# power-manager.net
KiCad netlist of a schematic drawn in EAGLE
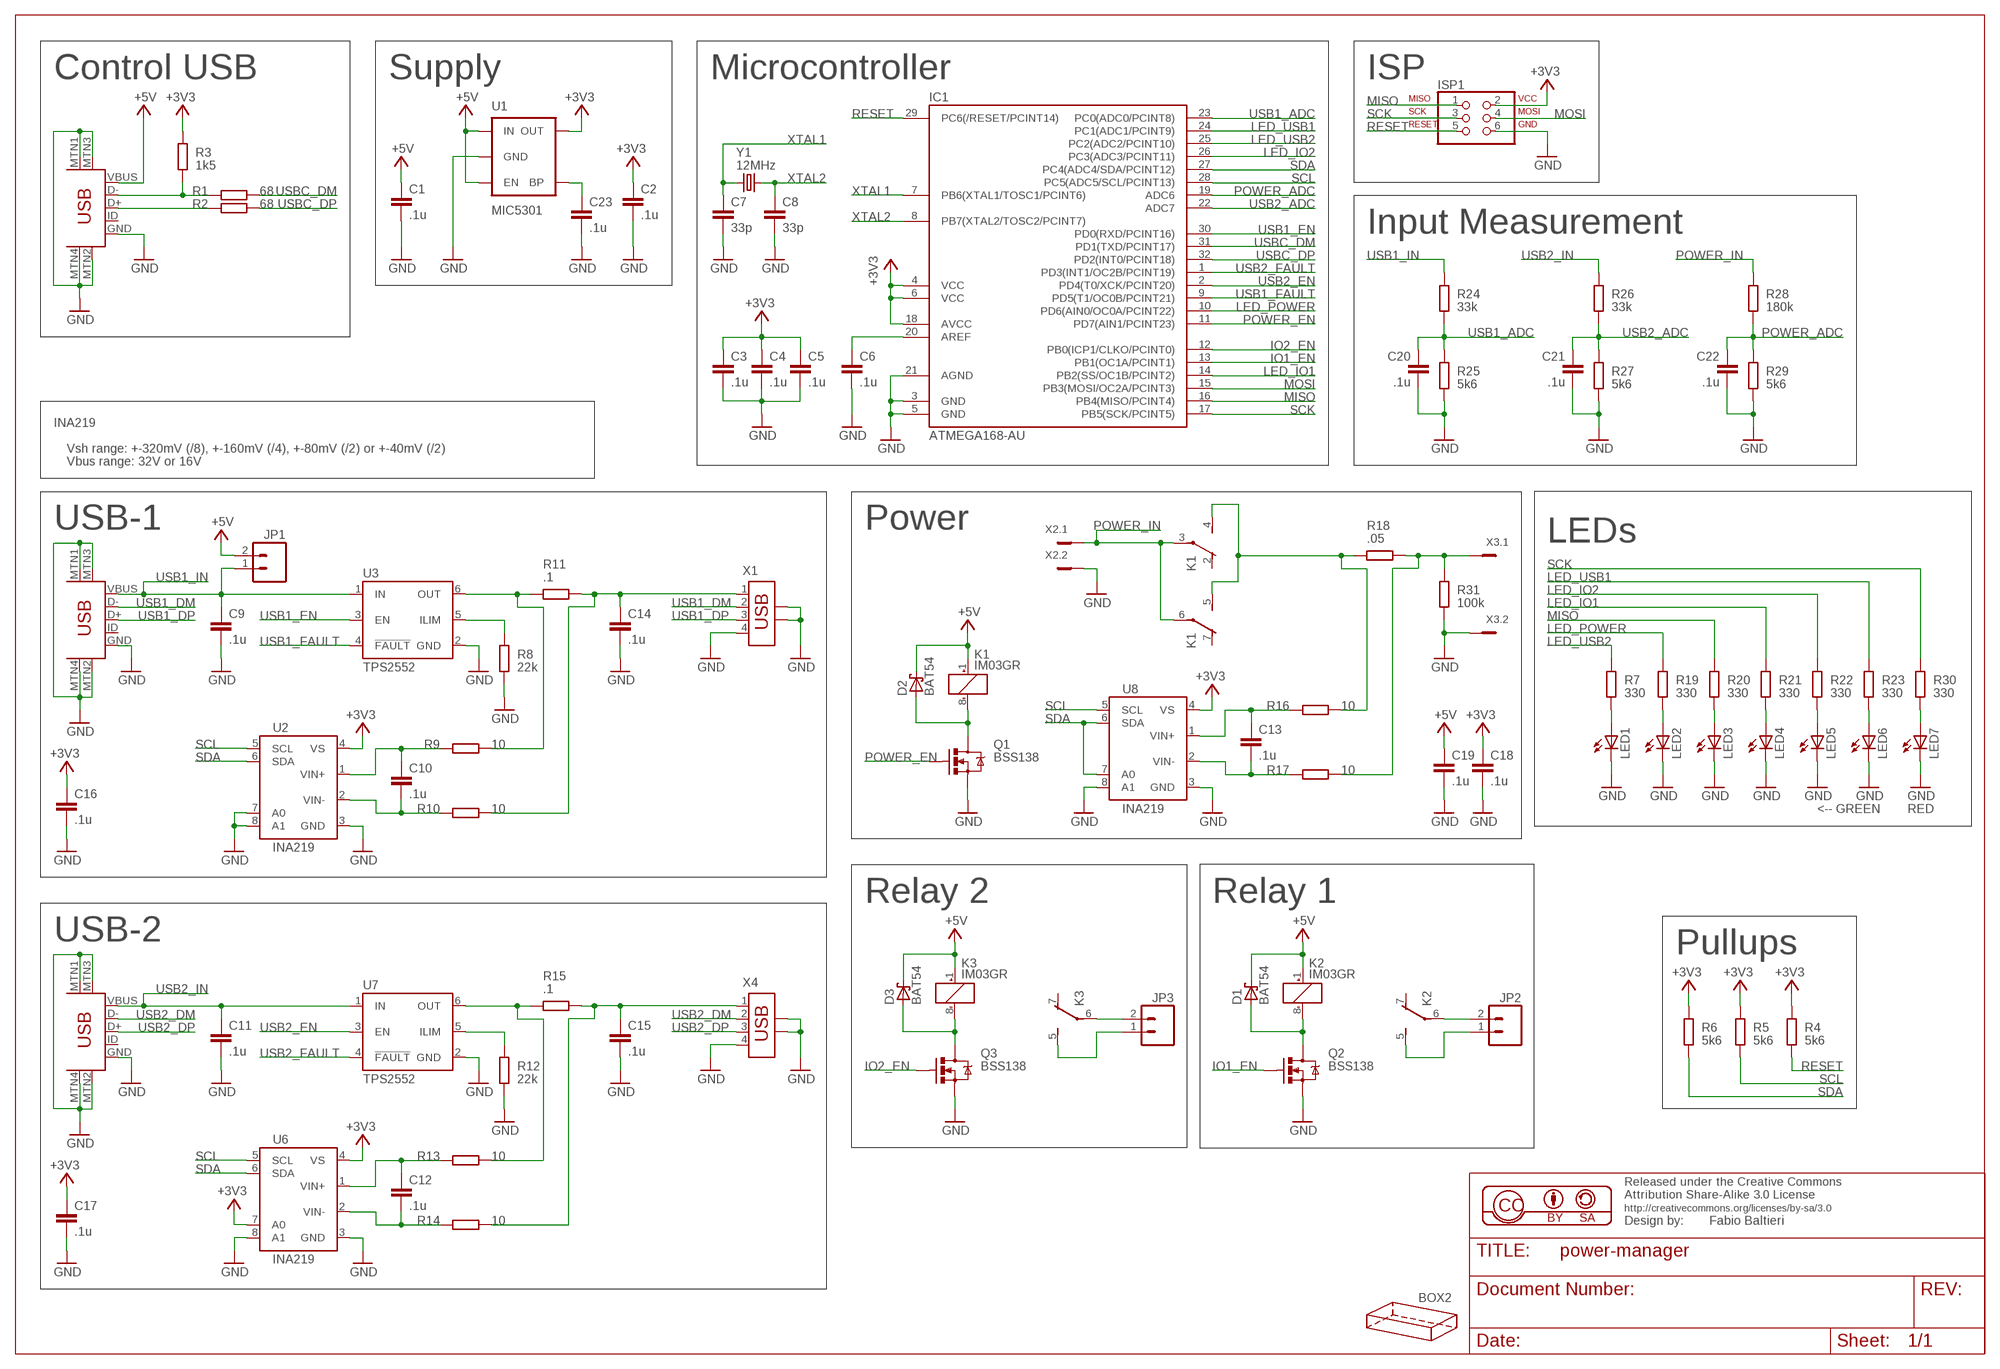
[diagram p0: schematic, sheet 1]

(export (version "E")
  (design (tool "Eeschema 10.0.6"))
  (components
    (comp (ref "BOX2")
      (value "HAMMOND-BOX-K")
      (footprint "eagle-import:1551K")
      (libsource (lib "eagle-import") (part "HAMMOND-BOX-K"))
    )
    (comp (ref "C1")
      (value ".1u")
      (footprint "eagle-import:C0805")
      (libsource (lib "eagle-import") (part "C-EUC0805"))
    )
    (comp (ref "C2")
      (value ".1u")
      (footprint "eagle-import:C0805")
      (libsource (lib "eagle-import") (part "C-EUC0805"))
    )
    (comp (ref "C3")
      (value ".1u")
      (footprint "eagle-import:C0805")
      (libsource (lib "eagle-import") (part "C-EUC0805"))
    )
    (comp (ref "C4")
      (value ".1u")
      (footprint "eagle-import:C0805")
      (libsource (lib "eagle-import") (part "C-EUC0805"))
    )
    (comp (ref "C5")
      (value ".1u")
      (footprint "eagle-import:C0805")
      (libsource (lib "eagle-import") (part "C-EUC0805"))
    )
    (comp (ref "C6")
      (value ".1u")
      (footprint "eagle-import:C0805")
      (libsource (lib "eagle-import") (part "C-EUC0805"))
    )
    (comp (ref "C7")
      (value "33p")
      (footprint "eagle-import:C0805")
      (libsource (lib "eagle-import") (part "C-EUC0805"))
    )
    (comp (ref "C8")
      (value "33p")
      (footprint "eagle-import:C0805")
      (libsource (lib "eagle-import") (part "C-EUC0805"))
    )
    (comp (ref "C9")
      (value ".1u")
      (footprint "eagle-import:C0805")
      (libsource (lib "eagle-import") (part "C-EUC0805"))
    )
    (comp (ref "C10")
      (value ".1u")
      (footprint "eagle-import:C0805")
      (libsource (lib "eagle-import") (part "C-EUC0805"))
    )
    (comp (ref "C11")
      (value ".1u")
      (footprint "eagle-import:C0805")
      (libsource (lib "eagle-import") (part "C-EUC0805"))
    )
    (comp (ref "C12")
      (value ".1u")
      (footprint "eagle-import:C0805")
      (libsource (lib "eagle-import") (part "C-EUC0805"))
    )
    (comp (ref "C13")
      (value ".1u")
      (footprint "eagle-import:C0805")
      (libsource (lib "eagle-import") (part "C-EUC0805"))
    )
    (comp (ref "C14")
      (value ".1u")
      (footprint "eagle-import:C0805")
      (libsource (lib "eagle-import") (part "C-EUC0805"))
    )
    (comp (ref "C15")
      (value ".1u")
      (footprint "eagle-import:C0805")
      (libsource (lib "eagle-import") (part "C-EUC0805"))
    )
    (comp (ref "C16")
      (value ".1u")
      (footprint "eagle-import:C0805")
      (libsource (lib "eagle-import") (part "C-EUC0805"))
    )
    (comp (ref "C17")
      (value ".1u")
      (footprint "eagle-import:C0805")
      (libsource (lib "eagle-import") (part "C-EUC0805"))
    )
    (comp (ref "C18")
      (value ".1u")
      (footprint "eagle-import:C0805")
      (libsource (lib "eagle-import") (part "C-EUC0805"))
    )
    (comp (ref "C19")
      (value ".1u")
      (footprint "eagle-import:C0805")
      (libsource (lib "eagle-import") (part "C-EUC0805"))
    )
    (comp (ref "C20")
      (value ".1u")
      (footprint "eagle-import:C0805")
      (libsource (lib "eagle-import") (part "C-EUC0805"))
    )
    (comp (ref "C21")
      (value ".1u")
      (footprint "eagle-import:C0805")
      (libsource (lib "eagle-import") (part "C-EUC0805"))
    )
    (comp (ref "C22")
      (value ".1u")
      (footprint "eagle-import:C0805")
      (libsource (lib "eagle-import") (part "C-EUC0805"))
    )
    (comp (ref "C23")
      (value ".1u")
      (footprint "eagle-import:C0805")
      (libsource (lib "eagle-import") (part "C-EUC0805"))
    )
    (comp (ref "D1")
      (value "BAT54")
      (footprint "eagle-import:SOT23")
      (libsource (lib "eagle-import") (part "BAT54"))
    )
    (comp (ref "D2")
      (value "BAT54")
      (footprint "eagle-import:SOT23")
      (libsource (lib "eagle-import") (part "BAT54"))
    )
    (comp (ref "D3")
      (value "BAT54")
      (footprint "eagle-import:SOT23")
      (libsource (lib "eagle-import") (part "BAT54"))
    )
    (comp (ref "IC1")
      (value "ATMEGA168-AU")
      (footprint "eagle-import:TQFP32-08")
      (libsource (lib "eagle-import") (part "ATMEGA168-AU"))
    )
    (comp (ref "ISP1")
      (value "ISP-AVR910PTH")
      (footprint "eagle-import:2X03")
      (libsource (lib "eagle-import") (part "ISP-AVR910PTH"))
    )
    (comp (ref "JP1")
      (value "M02PTH")
      (footprint "eagle-import:1X02")
      (libsource (lib "eagle-import") (part "M02PTH"))
    )
    (comp (ref "JP2")
      (value "M02PTH")
      (footprint "eagle-import:1X02")
      (libsource (lib "eagle-import") (part "M02PTH"))
    )
    (comp (ref "JP3")
      (value "M02PTH")
      (footprint "eagle-import:1X02")
      (libsource (lib "eagle-import") (part "M02PTH"))
    )
    (comp (ref "K1")
      (value "IM03GR")
      (footprint "eagle-import:G6J-2FL-Y")
      (fields (field (name "MPN") "G6J-2FL-Y-TR DC4.5"))
      (libsource (lib "eagle-import") (part "G6J-2?-YFL"))
    )
    (comp (ref "K2")
      (value "IM03GR")
      (footprint "eagle-import:G6J-2FL-Y")
      (fields (field (name "MPN") "G6J-2FL-Y-TR DC4.5"))
      (libsource (lib "eagle-import") (part "G6J-2?-YFL"))
    )
    (comp (ref "K3")
      (value "IM03GR")
      (footprint "eagle-import:G6J-2FL-Y")
      (fields (field (name "MPN") "G6J-2FL-Y-TR DC4.5"))
      (libsource (lib "eagle-import") (part "G6J-2?-YFL"))
    )
    (comp (ref "LED1")
      (value "LEDSML0805")
      (footprint "eagle-import:SML0805")
      (libsource (lib "eagle-import") (part "LEDSML0805"))
    )
    (comp (ref "LED2")
      (value "LEDSML0805")
      (footprint "eagle-import:SML0805")
      (libsource (lib "eagle-import") (part "LEDSML0805"))
    )
    (comp (ref "LED3")
      (value "LEDSML0805")
      (footprint "eagle-import:SML0805")
      (libsource (lib "eagle-import") (part "LEDSML0805"))
    )
    (comp (ref "LED4")
      (value "LEDSML0805")
      (footprint "eagle-import:SML0805")
      (libsource (lib "eagle-import") (part "LEDSML0805"))
    )
    (comp (ref "LED5")
      (value "LEDSML0805")
      (footprint "eagle-import:SML0805")
      (libsource (lib "eagle-import") (part "LEDSML0805"))
    )
    (comp (ref "LED6")
      (value "LEDSML0805")
      (footprint "eagle-import:SML0805")
      (libsource (lib "eagle-import") (part "LEDSML0805"))
    )
    (comp (ref "LED7")
      (value "LEDSML0805")
      (footprint "eagle-import:SML0805")
      (libsource (lib "eagle-import") (part "LEDSML0805"))
    )
    (comp (ref "Q1")
      (value "BSS138")
      (footprint "eagle-import:SOT23-3")
      (libsource (lib "eagle-import") (part "BSS138TRANS-00830"))
    )
    (comp (ref "Q2")
      (value "BSS138")
      (footprint "eagle-import:SOT23-3")
      (libsource (lib "eagle-import") (part "BSS138TRANS-00830"))
    )
    (comp (ref "Q3")
      (value "BSS138")
      (footprint "eagle-import:SOT23-3")
      (libsource (lib "eagle-import") (part "BSS138TRANS-00830"))
    )
    (comp (ref "R1")
      (value "68")
      (footprint "eagle-import:R0603")
      (libsource (lib "eagle-import") (part "R-EU_R0603"))
    )
    (comp (ref "R2")
      (value "68")
      (footprint "eagle-import:R0603")
      (libsource (lib "eagle-import") (part "R-EU_R0603"))
    )
    (comp (ref "R3")
      (value "1k5")
      (footprint "eagle-import:R0603")
      (libsource (lib "eagle-import") (part "R-EU_R0603"))
    )
    (comp (ref "R4")
      (value "5k6")
      (footprint "eagle-import:R0603")
      (libsource (lib "eagle-import") (part "R-EU_R0603"))
    )
    (comp (ref "R5")
      (value "5k6")
      (footprint "eagle-import:R0603")
      (libsource (lib "eagle-import") (part "R-EU_R0603"))
    )
    (comp (ref "R6")
      (value "5k6")
      (footprint "eagle-import:R0603")
      (libsource (lib "eagle-import") (part "R-EU_R0603"))
    )
    (comp (ref "R7")
      (value "330")
      (footprint "eagle-import:R0603")
      (libsource (lib "eagle-import") (part "R-EU_R0603"))
    )
    (comp (ref "R8")
      (value "22k")
      (footprint "eagle-import:R0603")
      (libsource (lib "eagle-import") (part "R-EU_R0603"))
    )
    (comp (ref "R9")
      (value "10")
      (footprint "eagle-import:R0603")
      (libsource (lib "eagle-import") (part "R-EU_R0603"))
    )
    (comp (ref "R10")
      (value "10")
      (footprint "eagle-import:R0603")
      (libsource (lib "eagle-import") (part "R-EU_R0603"))
    )
    (comp (ref "R11")
      (value ".1")
      (footprint "eagle-import:R0805")
      (libsource (lib "eagle-import") (part "R-EU_R0805"))
    )
    (comp (ref "R12")
      (value "22k")
      (footprint "eagle-import:R0603")
      (libsource (lib "eagle-import") (part "R-EU_R0603"))
    )
    (comp (ref "R13")
      (value "10")
      (footprint "eagle-import:R0603")
      (libsource (lib "eagle-import") (part "R-EU_R0603"))
    )
    (comp (ref "R14")
      (value "10")
      (footprint "eagle-import:R0603")
      (libsource (lib "eagle-import") (part "R-EU_R0603"))
    )
    (comp (ref "R15")
      (value ".1")
      (footprint "eagle-import:R0805")
      (libsource (lib "eagle-import") (part "R-EU_R0805"))
    )
    (comp (ref "R16")
      (value "10")
      (footprint "eagle-import:R0603")
      (libsource (lib "eagle-import") (part "R-EU_R0603"))
    )
    (comp (ref "R17")
      (value "10")
      (footprint "eagle-import:R0603")
      (libsource (lib "eagle-import") (part "R-EU_R0603"))
    )
    (comp (ref "R18")
      (value ".05")
      (footprint "eagle-import:R0805")
      (libsource (lib "eagle-import") (part "R-EU_R0805"))
    )
    (comp (ref "R19")
      (value "330")
      (footprint "eagle-import:R0603")
      (libsource (lib "eagle-import") (part "R-EU_R0603"))
    )
    (comp (ref "R20")
      (value "330")
      (footprint "eagle-import:R0603")
      (libsource (lib "eagle-import") (part "R-EU_R0603"))
    )
    (comp (ref "R21")
      (value "330")
      (footprint "eagle-import:R0603")
      (libsource (lib "eagle-import") (part "R-EU_R0603"))
    )
    (comp (ref "R22")
      (value "330")
      (footprint "eagle-import:R0603")
      (libsource (lib "eagle-import") (part "R-EU_R0603"))
    )
    (comp (ref "R23")
      (value "330")
      (footprint "eagle-import:R0603")
      (libsource (lib "eagle-import") (part "R-EU_R0603"))
    )
    (comp (ref "R24")
      (value "33k")
      (footprint "eagle-import:R0603")
      (libsource (lib "eagle-import") (part "R-EU_R0603"))
    )
    (comp (ref "R25")
      (value "5k6")
      (footprint "eagle-import:R0603")
      (libsource (lib "eagle-import") (part "R-EU_R0603"))
    )
    (comp (ref "R26")
      (value "33k")
      (footprint "eagle-import:R0603")
      (libsource (lib "eagle-import") (part "R-EU_R0603"))
    )
    (comp (ref "R27")
      (value "5k6")
      (footprint "eagle-import:R0603")
      (libsource (lib "eagle-import") (part "R-EU_R0603"))
    )
    (comp (ref "R28")
      (value "180k")
      (footprint "eagle-import:R0603")
      (libsource (lib "eagle-import") (part "R-EU_R0603"))
    )
    (comp (ref "R29")
      (value "5k6")
      (footprint "eagle-import:R0603")
      (libsource (lib "eagle-import") (part "R-EU_R0603"))
    )
    (comp (ref "R30")
      (value "330")
      (footprint "eagle-import:R0603")
      (libsource (lib "eagle-import") (part "R-EU_R0603"))
    )
    (comp (ref "R31")
      (value "100k")
      (footprint "eagle-import:R0603")
      (libsource (lib "eagle-import") (part "R-EU_R0603"))
    )
    (comp (ref "U$1")
      (value "USB-MINIB-5PIN")
      (footprint "eagle-import:USB-MINIB")
      (libsource (lib "eagle-import") (part "USB-MINIB-5PIN"))
    )
    (comp (ref "U$2")
      (value "USB-MINIB-5PIN")
      (footprint "eagle-import:USB-MINIB")
      (libsource (lib "eagle-import") (part "USB-MINIB-5PIN"))
    )
    (comp (ref "U$3")
      (value "USB-MINIB-5PIN")
      (footprint "eagle-import:USB-MINIB")
      (libsource (lib "eagle-import") (part "USB-MINIB-5PIN"))
    )
    (comp (ref "U1")
      (value "MIC5301")
      (footprint "eagle-import:SOT23-5")
      (libsource (lib "eagle-import") (part "V_REG_LDOSMD"))
    )
    (comp (ref "U2")
      (value "INA219")
      (footprint "eagle-import:SOT23-8L")
      (libsource (lib "eagle-import") (part "INA219"))
    )
    (comp (ref "U3")
      (value "TPS2552")
      (footprint "eagle-import:SOT23-6L")
      (libsource (lib "eagle-import") (part "TPS2552"))
    )
    (comp (ref "U6")
      (value "INA219")
      (footprint "eagle-import:SOT23-8L")
      (libsource (lib "eagle-import") (part "INA219"))
    )
    (comp (ref "U7")
      (value "TPS2552")
      (footprint "eagle-import:SOT23-6L")
      (libsource (lib "eagle-import") (part "TPS2552"))
    )
    (comp (ref "U8")
      (value "INA219")
      (footprint "eagle-import:SOT23-8L")
      (libsource (lib "eagle-import") (part "INA219"))
    )
    (comp (ref "X1")
      (value "USB-787616")
      (footprint "eagle-import:USB")
      (libsource (lib "eagle-import") (part "USB-787616"))
    )
    (comp (ref "X2")
      (value "MC2")
      (footprint "eagle-import:MC2")
      (libsource (lib "eagle-import") (part "MC2"))
    )
    (comp (ref "X3")
      (value "MC2")
      (footprint "eagle-import:MC2")
      (libsource (lib "eagle-import") (part "MC2"))
    )
    (comp (ref "X4")
      (value "USB-787616")
      (footprint "eagle-import:USB")
      (libsource (lib "eagle-import") (part "USB-787616"))
    )
    (comp (ref "Y1")
      (value "12MHz")
      (footprint "eagle-import:CRYSTAL-SMD-5X3")
      (libsource (lib "eagle-import") (part "CRYSTAL5X3"))
    )
  )
  (nets
    (net (code "1") (name "+3V3") (class "Default")
      (node (ref "C16") (pin "1") (pinfunction "1_1") (pintype "passive"))
      (node (ref "C17") (pin "1") (pinfunction "1_1") (pintype "passive"))
      (node (ref "C18") (pin "1") (pinfunction "1_1") (pintype "passive"))
      (node (ref "C2") (pin "1") (pinfunction "1_1") (pintype "passive"))
      (node (ref "C3") (pin "1") (pinfunction "1_1") (pintype "passive"))
      (node (ref "C4") (pin "1") (pinfunction "1_1") (pintype "passive"))
      (node (ref "C5") (pin "1") (pinfunction "1_1") (pintype "passive"))
      (node (ref "IC1") (pin "18") (pinfunction "AVCC_18") (pintype "passive"))
      (node (ref "IC1") (pin "4") (pinfunction "VCC_4") (pintype "power_in"))
      (node (ref "IC1") (pin "6") (pinfunction "VCC_6") (pintype "power_in"))
      (node (ref "ISP1") (pin "2") (pinfunction "2_2") (pintype "passive"))
      (node (ref "R3") (pin "1") (pinfunction "1_1") (pintype "passive"))
      (node (ref "R4") (pin "1") (pinfunction "1_1") (pintype "passive"))
      (node (ref "R5") (pin "1") (pinfunction "1_1") (pintype "passive"))
      (node (ref "R6") (pin "1") (pinfunction "1_1") (pintype "passive"))
      (node (ref "U1") (pin "5") (pinfunction "OUT_5") (pintype "passive"))
      (node (ref "U2") (pin "4") (pinfunction "VS_4") (pintype "bidirectional"))
      (node (ref "U6") (pin "4") (pinfunction "VS_4") (pintype "bidirectional"))
      (node (ref "U6") (pin "7") (pinfunction "A0_7") (pintype "bidirectional"))
      (node (ref "U8") (pin "4") (pinfunction "VS_4") (pintype "bidirectional"))
    )
    (net (code "2") (name "+5V") (class "Default")
      (node (ref "C1") (pin "1") (pinfunction "1_1") (pintype "passive"))
      (node (ref "C19") (pin "1") (pinfunction "1_1") (pintype "passive"))
      (node (ref "D1") (pin "3") (pinfunction "C_3") (pintype "passive"))
      (node (ref "D2") (pin "3") (pinfunction "C_3") (pintype "passive"))
      (node (ref "D3") (pin "3") (pinfunction "C_3") (pintype "passive"))
      (node (ref "JP1") (pin "2") (pinfunction "2_2") (pintype "passive"))
      (node (ref "K1") (pin "1") (pinfunction "+_1") (pintype "passive"))
      (node (ref "K2") (pin "1") (pinfunction "+_1") (pintype "passive"))
      (node (ref "K3") (pin "1") (pinfunction "+_1") (pintype "passive"))
      (node (ref "U$1") (pin "VBUS") (pinfunction "VBUS_VBUS") (pintype "bidirectional"))
      (node (ref "U1") (pin "1") (pinfunction "IN_1") (pintype "input"))
      (node (ref "U1") (pin "3") (pinfunction "EN_3") (pintype "input"))
    )
    (net (code "3") (name "/IO1_EN") (class "Default")
      (node (ref "IC1") (pin "13") (pinfunction "PB1(OC1A/PCINT1)_13") (pintype "bidirectional"))
      (node (ref "Q2") (pin "1") (pinfunction "G_1") (pintype "passive"))
    )
    (net (code "4") (name "/IO2_EN") (class "Default")
      (node (ref "IC1") (pin "12") (pinfunction "PB0(ICP1/CLKO/PCINT0)_12") (pintype "bidirectional"))
      (node (ref "Q3") (pin "1") (pinfunction "G_1") (pintype "passive"))
    )
    (net (code "5") (name "/LED_IO1") (class "Default")
      (node (ref "IC1") (pin "14") (pinfunction "PB2(SS/OC1B/PCINT2)_14") (pintype "bidirectional"))
      (node (ref "R21") (pin "1") (pinfunction "1_1") (pintype "passive"))
    )
    (net (code "6") (name "/LED_IO2") (class "Default")
      (node (ref "IC1") (pin "26") (pinfunction "PC3(ADC3/PCINT11)_26") (pintype "bidirectional"))
      (node (ref "R22") (pin "1") (pinfunction "1_1") (pintype "passive"))
    )
    (net (code "7") (name "/LED_POWER") (class "Default")
      (node (ref "IC1") (pin "10") (pinfunction "PD6(AIN0/OC0A/PCINT22)_10") (pintype "bidirectional"))
      (node (ref "R19") (pin "1") (pinfunction "1_1") (pintype "passive"))
    )
    (net (code "8") (name "/LED_USB1") (class "Default")
      (node (ref "IC1") (pin "24") (pinfunction "PC1(ADC1/PCINT9)_24") (pintype "bidirectional"))
      (node (ref "R23") (pin "1") (pinfunction "1_1") (pintype "passive"))
    )
    (net (code "9") (name "/LED_USB2") (class "Default")
      (node (ref "IC1") (pin "25") (pinfunction "PC2(ADC2/PCINT10)_25") (pintype "bidirectional"))
      (node (ref "R7") (pin "1") (pinfunction "1_1") (pintype "passive"))
    )
    (net (code "10") (name "/MISO") (class "Default")
      (node (ref "IC1") (pin "16") (pinfunction "PB4(MISO/PCINT4)_16") (pintype "bidirectional"))
      (node (ref "ISP1") (pin "1") (pinfunction "1_1") (pintype "passive"))
      (node (ref "R20") (pin "1") (pinfunction "1_1") (pintype "passive"))
    )
    (net (code "11") (name "/MOSI") (class "Default")
      (node (ref "IC1") (pin "15") (pinfunction "PB3(MOSI/OC2A/PCINT3)_15") (pintype "bidirectional"))
      (node (ref "ISP1") (pin "4") (pinfunction "4_4") (pintype "passive"))
    )
    (net (code "12") (name "/POWER_ADC") (class "Default")
      (node (ref "C22") (pin "1") (pinfunction "1_1") (pintype "passive"))
      (node (ref "IC1") (pin "19") (pinfunction "ADC6_19") (pintype "passive"))
      (node (ref "R28") (pin "2") (pinfunction "2_2") (pintype "passive"))
      (node (ref "R29") (pin "1") (pinfunction "1_1") (pintype "passive"))
    )
    (net (code "13") (name "/POWER_EN") (class "Default")
      (node (ref "IC1") (pin "11") (pinfunction "PD7(AIN1/PCINT23)_11") (pintype "bidirectional"))
      (node (ref "Q1") (pin "1") (pinfunction "G_1") (pintype "passive"))
    )
    (net (code "14") (name "/POWER_IN") (class "Default")
      (node (ref "K1") (pin "3") (pinfunction "P_3") (pintype "passive"))
      (node (ref "K1") (pin "6") (pinfunction "P_6") (pintype "passive"))
      (node (ref "R28") (pin "1") (pinfunction "1_1") (pintype "passive"))
      (node (ref "X2") (pin "1") (pinfunction "SK_1") (pintype "passive"))
    )
    (net (code "15") (name "/RESET") (class "Default")
      (node (ref "IC1") (pin "29") (pinfunction "PC6(/RESET/PCINT14)_29") (pintype "bidirectional"))
      (node (ref "ISP1") (pin "5") (pinfunction "5_5") (pintype "passive"))
      (node (ref "R4") (pin "2") (pinfunction "2_2") (pintype "passive"))
    )
    (net (code "16") (name "/SCK") (class "Default")
      (node (ref "IC1") (pin "17") (pinfunction "PB5(SCK/PCINT5)_17") (pintype "bidirectional"))
      (node (ref "ISP1") (pin "3") (pinfunction "3_3") (pintype "passive"))
      (node (ref "R30") (pin "1") (pinfunction "1_1") (pintype "passive"))
    )
    (net (code "17") (name "/SCL") (class "Default")
      (node (ref "IC1") (pin "28") (pinfunction "PC5(ADC5/SCL/PCINT13)_28") (pintype "bidirectional"))
      (node (ref "R5") (pin "2") (pinfunction "2_2") (pintype "passive"))
      (node (ref "U2") (pin "5") (pinfunction "SCL_5") (pintype "bidirectional"))
      (node (ref "U6") (pin "5") (pinfunction "SCL_5") (pintype "bidirectional"))
      (node (ref "U8") (pin "5") (pinfunction "SCL_5") (pintype "bidirectional"))
    )
    (net (code "18") (name "/SDA") (class "Default")
      (node (ref "IC1") (pin "27") (pinfunction "PC4(ADC4/SDA/PCINT12)_27") (pintype "bidirectional"))
      (node (ref "R6") (pin "2") (pinfunction "2_2") (pintype "passive"))
      (node (ref "U2") (pin "6") (pinfunction "SDA_6") (pintype "bidirectional"))
      (node (ref "U6") (pin "6") (pinfunction "SDA_6") (pintype "bidirectional"))
      (node (ref "U8") (pin "6") (pinfunction "SDA_6") (pintype "bidirectional"))
      (node (ref "U8") (pin "7") (pinfunction "A0_7") (pintype "bidirectional"))
    )
    (net (code "19") (name "/USB1_ADC") (class "Default")
      (node (ref "C20") (pin "1") (pinfunction "1_1") (pintype "passive"))
      (node (ref "IC1") (pin "23") (pinfunction "PC0(ADC0/PCINT8)_23") (pintype "bidirectional"))
      (node (ref "R24") (pin "2") (pinfunction "2_2") (pintype "passive"))
      (node (ref "R25") (pin "1") (pinfunction "1_1") (pintype "passive"))
    )
    (net (code "20") (name "/USB1_DM") (class "Default")
      (node (ref "U$2") (pin "D-") (pinfunction "D-_D-") (pintype "bidirectional"))
      (node (ref "X1") (pin "2") (pinfunction "2_2") (pintype "passive"))
    )
    (net (code "21") (name "/USB1_DP") (class "Default")
      (node (ref "U$2") (pin "D+") (pinfunction "D+_D+") (pintype "bidirectional"))
      (node (ref "X1") (pin "3") (pinfunction "3_3") (pintype "passive"))
    )
    (net (code "22") (name "/USB1_EN") (class "Default")
      (node (ref "IC1") (pin "30") (pinfunction "PD0(RXD/PCINT16)_30") (pintype "bidirectional"))
      (node (ref "U3") (pin "3") (pinfunction "EN_3") (pintype "bidirectional"))
    )
    (net (code "23") (name "/USB1_FAULT") (class "Default")
      (node (ref "IC1") (pin "9") (pinfunction "PD5(T1/OC0B/PCINT21)_9") (pintype "bidirectional"))
      (node (ref "U3") (pin "4") (pinfunction "~{FAULT}_4") (pintype "bidirectional"))
    )
    (net (code "24") (name "/USB1_IN") (class "Default")
      (node (ref "C9") (pin "1") (pinfunction "1_1") (pintype "passive"))
      (node (ref "JP1") (pin "1") (pinfunction "1_1") (pintype "passive"))
      (node (ref "R24") (pin "1") (pinfunction "1_1") (pintype "passive"))
      (node (ref "U$2") (pin "VBUS") (pinfunction "VBUS_VBUS") (pintype "bidirectional"))
      (node (ref "U3") (pin "1") (pinfunction "IN_1") (pintype "bidirectional"))
    )
    (net (code "25") (name "/USB2_ADC") (class "Default")
      (node (ref "C21") (pin "1") (pinfunction "1_1") (pintype "passive"))
      (node (ref "IC1") (pin "22") (pinfunction "ADC7_22") (pintype "passive"))
      (node (ref "R26") (pin "2") (pinfunction "2_2") (pintype "passive"))
      (node (ref "R27") (pin "1") (pinfunction "1_1") (pintype "passive"))
    )
    (net (code "26") (name "/USB2_DM") (class "Default")
      (node (ref "U$3") (pin "D-") (pinfunction "D-_D-") (pintype "bidirectional"))
      (node (ref "X4") (pin "2") (pinfunction "2_2") (pintype "passive"))
    )
    (net (code "27") (name "/USB2_DP") (class "Default")
      (node (ref "U$3") (pin "D+") (pinfunction "D+_D+") (pintype "bidirectional"))
      (node (ref "X4") (pin "3") (pinfunction "3_3") (pintype "passive"))
    )
    (net (code "28") (name "/USB2_EN") (class "Default")
      (node (ref "IC1") (pin "2") (pinfunction "PD4(T0/XCK/PCINT20)_2") (pintype "bidirectional"))
      (node (ref "U7") (pin "3") (pinfunction "EN_3") (pintype "bidirectional"))
    )
    (net (code "29") (name "/USB2_FAULT") (class "Default")
      (node (ref "IC1") (pin "1") (pinfunction "PD3(INT1/OC2B/PCINT19)_1") (pintype "bidirectional"))
      (node (ref "U7") (pin "4") (pinfunction "~{FAULT}_4") (pintype "bidirectional"))
    )
    (net (code "30") (name "/USB2_IN") (class "Default")
      (node (ref "C11") (pin "1") (pinfunction "1_1") (pintype "passive"))
      (node (ref "R26") (pin "1") (pinfunction "1_1") (pintype "passive"))
      (node (ref "U$3") (pin "VBUS") (pinfunction "VBUS_VBUS") (pintype "bidirectional"))
      (node (ref "U7") (pin "1") (pinfunction "IN_1") (pintype "bidirectional"))
    )
    (net (code "31") (name "/USBC_DM") (class "Default")
      (node (ref "IC1") (pin "31") (pinfunction "PD1(TXD/PCINT17)_31") (pintype "bidirectional"))
      (node (ref "R1") (pin "2") (pinfunction "2_2") (pintype "passive"))
    )
    (net (code "32") (name "/USBC_DP") (class "Default")
      (node (ref "IC1") (pin "32") (pinfunction "PD2(INT0/PCINT18)_32") (pintype "bidirectional"))
      (node (ref "R2") (pin "2") (pinfunction "2_2") (pintype "passive"))
    )
    (net (code "33") (name "/XTAL1") (class "Default")
      (node (ref "C7") (pin "1") (pinfunction "1_1") (pintype "passive"))
      (node (ref "IC1") (pin "7") (pinfunction "PB6(XTAL1/TOSC1/PCINT6)_7") (pintype "bidirectional"))
      (node (ref "Y1") (pin "1") (pinfunction "1_1") (pintype "passive"))
    )
    (net (code "34") (name "/XTAL2") (class "Default")
      (node (ref "C8") (pin "1") (pinfunction "1_1") (pintype "passive"))
      (node (ref "IC1") (pin "8") (pinfunction "PB7(XTAL2/TOSC2/PCINT7)_8") (pintype "bidirectional"))
      (node (ref "Y1") (pin "3") (pinfunction "2_3") (pintype "passive"))
    )
    (net (code "35") (name "GND") (class "Default")
      (node (ref "C1") (pin "2") (pinfunction "2_2") (pintype "passive"))
      (node (ref "C11") (pin "2") (pinfunction "2_2") (pintype "passive"))
      (node (ref "C14") (pin "2") (pinfunction "2_2") (pintype "passive"))
      (node (ref "C15") (pin "2") (pinfunction "2_2") (pintype "passive"))
      (node (ref "C16") (pin "2") (pinfunction "2_2") (pintype "passive"))
      (node (ref "C17") (pin "2") (pinfunction "2_2") (pintype "passive"))
      (node (ref "C18") (pin "2") (pinfunction "2_2") (pintype "passive"))
      (node (ref "C19") (pin "2") (pinfunction "2_2") (pintype "passive"))
      (node (ref "C2") (pin "2") (pinfunction "2_2") (pintype "passive"))
      (node (ref "C20") (pin "2") (pinfunction "2_2") (pintype "passive"))
      (node (ref "C21") (pin "2") (pinfunction "2_2") (pintype "passive"))
      (node (ref "C22") (pin "2") (pinfunction "2_2") (pintype "passive"))
      (node (ref "C23") (pin "2") (pinfunction "2_2") (pintype "passive"))
      (node (ref "C3") (pin "2") (pinfunction "2_2") (pintype "passive"))
      (node (ref "C4") (pin "2") (pinfunction "2_2") (pintype "passive"))
      (node (ref "C5") (pin "2") (pinfunction "2_2") (pintype "passive"))
      (node (ref "C6") (pin "2") (pinfunction "2_2") (pintype "passive"))
      (node (ref "C7") (pin "2") (pinfunction "2_2") (pintype "passive"))
      (node (ref "C8") (pin "2") (pinfunction "2_2") (pintype "passive"))
      (node (ref "C9") (pin "2") (pinfunction "2_2") (pintype "passive"))
      (node (ref "IC1") (pin "21") (pinfunction "AGND_21") (pintype "power_in"))
      (node (ref "IC1") (pin "3") (pinfunction "GND_3") (pintype "power_in"))
      (node (ref "IC1") (pin "5") (pinfunction "GND_5") (pintype "power_in"))
      (node (ref "ISP1") (pin "6") (pinfunction "6_6") (pintype "passive"))
      (node (ref "LED1") (pin "C") (pinfunction "C_C") (pintype "passive"))
      (node (ref "LED2") (pin "C") (pinfunction "C_C") (pintype "passive"))
      (node (ref "LED3") (pin "C") (pinfunction "C_C") (pintype "passive"))
      (node (ref "LED4") (pin "C") (pinfunction "C_C") (pintype "passive"))
      (node (ref "LED5") (pin "C") (pinfunction "C_C") (pintype "passive"))
      (node (ref "LED6") (pin "C") (pinfunction "C_C") (pintype "passive"))
      (node (ref "LED7") (pin "C") (pinfunction "C_C") (pintype "passive"))
      (node (ref "Q1") (pin "2") (pinfunction "S_2") (pintype "passive"))
      (node (ref "Q2") (pin "2") (pinfunction "S_2") (pintype "passive"))
      (node (ref "Q3") (pin "2") (pinfunction "S_2") (pintype "passive"))
      (node (ref "R12") (pin "2") (pinfunction "2_2") (pintype "passive"))
      (node (ref "R25") (pin "2") (pinfunction "2_2") (pintype "passive"))
      (node (ref "R27") (pin "2") (pinfunction "2_2") (pintype "passive"))
      (node (ref "R29") (pin "2") (pinfunction "2_2") (pintype "passive"))
      (node (ref "R31") (pin "2") (pinfunction "2_2") (pintype "passive"))
      (node (ref "R8") (pin "2") (pinfunction "2_2") (pintype "passive"))
      (node (ref "U$1") (pin "GND") (pinfunction "GND_GND") (pintype "bidirectional"))
      (node (ref "U$1") (pin "MTN1") (pinfunction "MTN2_MTN1") (pintype "bidirectional"))
      (node (ref "U$1") (pin "MTN2") (pinfunction "MTN3_MTN2") (pintype "bidirectional"))
      (node (ref "U$1") (pin "MTN3") (pinfunction "MTN1_MTN3") (pintype "bidirectional"))
      (node (ref "U$1") (pin "MTN4") (pinfunction "MTN4_MTN4") (pintype "bidirectional"))
      (node (ref "U$2") (pin "GND") (pinfunction "GND_GND") (pintype "bidirectional"))
      (node (ref "U$2") (pin "MTN1") (pinfunction "MTN2_MTN1") (pintype "bidirectional"))
      (node (ref "U$2") (pin "MTN2") (pinfunction "MTN3_MTN2") (pintype "bidirectional"))
      (node (ref "U$2") (pin "MTN3") (pinfunction "MTN1_MTN3") (pintype "bidirectional"))
      (node (ref "U$2") (pin "MTN4") (pinfunction "MTN4_MTN4") (pintype "bidirectional"))
      (node (ref "U$3") (pin "GND") (pinfunction "GND_GND") (pintype "bidirectional"))
      (node (ref "U$3") (pin "MTN1") (pinfunction "MTN2_MTN1") (pintype "bidirectional"))
      (node (ref "U$3") (pin "MTN2") (pinfunction "MTN3_MTN2") (pintype "bidirectional"))
      (node (ref "U$3") (pin "MTN3") (pinfunction "MTN1_MTN3") (pintype "bidirectional"))
      (node (ref "U$3") (pin "MTN4") (pinfunction "MTN4_MTN4") (pintype "bidirectional"))
      (node (ref "U1") (pin "2") (pinfunction "GND_2") (pintype "input"))
      (node (ref "U2") (pin "3") (pinfunction "GND_3") (pintype "bidirectional"))
      (node (ref "U2") (pin "7") (pinfunction "A0_7") (pintype "bidirectional"))
      (node (ref "U2") (pin "8") (pinfunction "A1_8") (pintype "bidirectional"))
      (node (ref "U3") (pin "2") (pinfunction "GND_2") (pintype "bidirectional"))
      (node (ref "U6") (pin "3") (pinfunction "GND_3") (pintype "bidirectional"))
      (node (ref "U6") (pin "8") (pinfunction "A1_8") (pintype "bidirectional"))
      (node (ref "U7") (pin "2") (pinfunction "GND_2") (pintype "bidirectional"))
      (node (ref "U8") (pin "3") (pinfunction "GND_3") (pintype "bidirectional"))
      (node (ref "U8") (pin "8") (pinfunction "A1_8") (pintype "bidirectional"))
      (node (ref "X1") (pin "4") (pinfunction "4_4") (pintype "passive"))
      (node (ref "X1") (pin "SHLD1") (pinfunction "SHLD1_SHLD1") (pintype "passive"))
      (node (ref "X1") (pin "SHLD2") (pinfunction "SHLD2_SHLD2") (pintype "passive"))
      (node (ref "X2") (pin "2") (pinfunction "SK_2") (pintype "passive"))
      (node (ref "X3") (pin "2") (pinfunction "SK_2") (pintype "passive"))
      (node (ref "X4") (pin "4") (pinfunction "4_4") (pintype "passive"))
      (node (ref "X4") (pin "SHLD1") (pinfunction "SHLD1_SHLD1") (pintype "passive"))
      (node (ref "X4") (pin "SHLD2") (pinfunction "SHLD2_SHLD2") (pintype "passive"))
    )
    (net (code "36") (name "Net-(C14-Pad1)") (class "Default")
      (node (ref "C14") (pin "1") (pinfunction "1_1") (pintype "passive"))
      (node (ref "R10") (pin "2") (pinfunction "2_2") (pintype "passive"))
      (node (ref "R11") (pin "2") (pinfunction "2_2") (pintype "passive"))
      (node (ref "X1") (pin "1") (pinfunction "1_1") (pintype "passive"))
    )
    (net (code "37") (name "Net-(C15-Pad1)") (class "Default")
      (node (ref "C15") (pin "1") (pinfunction "1_1") (pintype "passive"))
      (node (ref "R14") (pin "2") (pinfunction "2_2") (pintype "passive"))
      (node (ref "R15") (pin "2") (pinfunction "2_2") (pintype "passive"))
      (node (ref "X4") (pin "1") (pinfunction "1_1") (pintype "passive"))
    )
    (net (code "38") (name "Net-(D1-A)") (class "Default")
      (node (ref "D1") (pin "1") (pinfunction "A_1") (pintype "passive"))
      (node (ref "K2") (pin "8") (pinfunction "-_8") (pintype "passive"))
      (node (ref "Q2") (pin "3") (pinfunction "D_3") (pintype "passive"))
    )
    (net (code "39") (name "Net-(D2-A)") (class "Default")
      (node (ref "D2") (pin "1") (pinfunction "A_1") (pintype "passive"))
      (node (ref "K1") (pin "8") (pinfunction "-_8") (pintype "passive"))
      (node (ref "Q1") (pin "3") (pinfunction "D_3") (pintype "passive"))
    )
    (net (code "40") (name "Net-(D3-A)") (class "Default")
      (node (ref "D3") (pin "1") (pinfunction "A_1") (pintype "passive"))
      (node (ref "K3") (pin "8") (pinfunction "-_8") (pintype "passive"))
      (node (ref "Q3") (pin "3") (pinfunction "D_3") (pintype "passive"))
    )
    (net (code "41") (name "Net-(IC1-AREF)") (class "Default")
      (node (ref "C6") (pin "1") (pinfunction "1_1") (pintype "passive"))
      (node (ref "IC1") (pin "20") (pinfunction "AREF_20") (pintype "passive"))
    )
    (net (code "42") (name "Net-(K1B-S)") (class "Default")
      (node (ref "K1") (pin "4") (pinfunction "S_4") (pintype "passive"))
      (node (ref "K1") (pin "5") (pinfunction "S_5") (pintype "passive"))
      (node (ref "R16") (pin "2") (pinfunction "2_2") (pintype "passive"))
      (node (ref "R18") (pin "1") (pinfunction "1_1") (pintype "passive"))
    )
    (net (code "43") (name "Net-(K2C-P)") (class "Default")
      (node (ref "JP2") (pin "2") (pinfunction "2_2") (pintype "passive"))
      (node (ref "K2") (pin "6") (pinfunction "P_6") (pintype "passive"))
    )
    (net (code "44") (name "Net-(K2C-S)") (class "Default")
      (node (ref "JP2") (pin "1") (pinfunction "1_1") (pintype "passive"))
      (node (ref "K2") (pin "5") (pinfunction "S_5") (pintype "passive"))
    )
    (net (code "45") (name "Net-(K3C-P)") (class "Default")
      (node (ref "JP3") (pin "2") (pinfunction "2_2") (pintype "passive"))
      (node (ref "K3") (pin "6") (pinfunction "P_6") (pintype "passive"))
    )
    (net (code "46") (name "Net-(K3C-S)") (class "Default")
      (node (ref "JP3") (pin "1") (pinfunction "1_1") (pintype "passive"))
      (node (ref "K3") (pin "5") (pinfunction "S_5") (pintype "passive"))
    )
    (net (code "47") (name "Net-(LED1-PadA)") (class "Default")
      (node (ref "LED1") (pin "A") (pinfunction "A_A") (pintype "passive"))
      (node (ref "R7") (pin "2") (pinfunction "2_2") (pintype "passive"))
    )
    (net (code "48") (name "Net-(LED2-PadA)") (class "Default")
      (node (ref "LED2") (pin "A") (pinfunction "A_A") (pintype "passive"))
      (node (ref "R19") (pin "2") (pinfunction "2_2") (pintype "passive"))
    )
    (net (code "49") (name "Net-(LED3-PadA)") (class "Default")
      (node (ref "LED3") (pin "A") (pinfunction "A_A") (pintype "passive"))
      (node (ref "R20") (pin "2") (pinfunction "2_2") (pintype "passive"))
    )
    (net (code "50") (name "Net-(LED4-PadA)") (class "Default")
      (node (ref "LED4") (pin "A") (pinfunction "A_A") (pintype "passive"))
      (node (ref "R21") (pin "2") (pinfunction "2_2") (pintype "passive"))
    )
    (net (code "51") (name "Net-(LED5-PadA)") (class "Default")
      (node (ref "LED5") (pin "A") (pinfunction "A_A") (pintype "passive"))
      (node (ref "R22") (pin "2") (pinfunction "2_2") (pintype "passive"))
    )
    (net (code "52") (name "Net-(LED6-PadA)") (class "Default")
      (node (ref "LED6") (pin "A") (pinfunction "A_A") (pintype "passive"))
      (node (ref "R23") (pin "2") (pinfunction "2_2") (pintype "passive"))
    )
    (net (code "53") (name "Net-(LED7-PadA)") (class "Default")
      (node (ref "LED7") (pin "A") (pinfunction "A_A") (pintype "passive"))
      (node (ref "R30") (pin "2") (pinfunction "2_2") (pintype "passive"))
    )
    (net (code "54") (name "Net-(R1-Pad1)") (class "Default")
      (node (ref "R1") (pin "1") (pinfunction "1_1") (pintype "passive"))
      (node (ref "R3") (pin "2") (pinfunction "2_2") (pintype "passive"))
      (node (ref "U$1") (pin "D-") (pinfunction "D-_D-") (pintype "bidirectional"))
    )
    (net (code "55") (name "Net-(R2-Pad1)") (class "Default")
      (node (ref "R2") (pin "1") (pinfunction "1_1") (pintype "passive"))
      (node (ref "U$1") (pin "D+") (pinfunction "D+_D+") (pintype "bidirectional"))
    )
    (net (code "56") (name "Net-(U1-BP)") (class "Default")
      (node (ref "C23") (pin "1") (pinfunction "1_1") (pintype "passive"))
      (node (ref "U1") (pin "4") (pinfunction "BP_4") (pintype "input"))
    )
    (net (code "57") (name "Net-(U2-VIN+)") (class "Default")
      (node (ref "C10") (pin "1") (pinfunction "1_1") (pintype "passive"))
      (node (ref "R9") (pin "1") (pinfunction "1_1") (pintype "passive"))
      (node (ref "U2") (pin "1") (pinfunction "VIN+_1") (pintype "bidirectional"))
    )
    (net (code "58") (name "Net-(U2-VIN-)") (class "Default")
      (node (ref "C10") (pin "2") (pinfunction "2_2") (pintype "passive"))
      (node (ref "R10") (pin "1") (pinfunction "1_1") (pintype "passive"))
      (node (ref "U2") (pin "2") (pinfunction "VIN-_2") (pintype "bidirectional"))
    )
    (net (code "59") (name "Net-(U3-ILIM)") (class "Default")
      (node (ref "R8") (pin "1") (pinfunction "1_1") (pintype "passive"))
      (node (ref "U3") (pin "5") (pinfunction "ILIM_5") (pintype "bidirectional"))
    )
    (net (code "60") (name "Net-(U3-OUT)") (class "Default")
      (node (ref "R11") (pin "1") (pinfunction "1_1") (pintype "passive"))
      (node (ref "R9") (pin "2") (pinfunction "2_2") (pintype "passive"))
      (node (ref "U3") (pin "6") (pinfunction "OUT_6") (pintype "bidirectional"))
    )
    (net (code "61") (name "Net-(U6-VIN+)") (class "Default")
      (node (ref "C12") (pin "1") (pinfunction "1_1") (pintype "passive"))
      (node (ref "R13") (pin "1") (pinfunction "1_1") (pintype "passive"))
      (node (ref "U6") (pin "1") (pinfunction "VIN+_1") (pintype "bidirectional"))
    )
    (net (code "62") (name "Net-(U6-VIN-)") (class "Default")
      (node (ref "C12") (pin "2") (pinfunction "2_2") (pintype "passive"))
      (node (ref "R14") (pin "1") (pinfunction "1_1") (pintype "passive"))
      (node (ref "U6") (pin "2") (pinfunction "VIN-_2") (pintype "bidirectional"))
    )
    (net (code "63") (name "Net-(U7-ILIM)") (class "Default")
      (node (ref "R12") (pin "1") (pinfunction "1_1") (pintype "passive"))
      (node (ref "U7") (pin "5") (pinfunction "ILIM_5") (pintype "bidirectional"))
    )
    (net (code "64") (name "Net-(U7-OUT)") (class "Default")
      (node (ref "R13") (pin "2") (pinfunction "2_2") (pintype "passive"))
      (node (ref "R15") (pin "1") (pinfunction "1_1") (pintype "passive"))
      (node (ref "U7") (pin "6") (pinfunction "OUT_6") (pintype "bidirectional"))
    )
    (net (code "65") (name "Net-(U8-VIN+)") (class "Default")
      (node (ref "C13") (pin "1") (pinfunction "1_1") (pintype "passive"))
      (node (ref "R16") (pin "1") (pinfunction "1_1") (pintype "passive"))
      (node (ref "U8") (pin "1") (pinfunction "VIN+_1") (pintype "bidirectional"))
    )
    (net (code "66") (name "Net-(U8-VIN-)") (class "Default")
      (node (ref "C13") (pin "2") (pinfunction "2_2") (pintype "passive"))
      (node (ref "R17") (pin "1") (pinfunction "1_1") (pintype "passive"))
      (node (ref "U8") (pin "2") (pinfunction "VIN-_2") (pintype "bidirectional"))
    )
    (net (code "67") (name "Net-(X3A-SK)") (class "Default")
      (node (ref "R17") (pin "2") (pinfunction "2_2") (pintype "passive"))
      (node (ref "R18") (pin "2") (pinfunction "2_2") (pintype "passive"))
      (node (ref "R31") (pin "1") (pinfunction "1_1") (pintype "passive"))
      (node (ref "X3") (pin "1") (pinfunction "SK_1") (pintype "passive"))
    )
    (net (code "68") (name "unconnected-(K1B-O-Pad2)") (class "Default")
      (node (ref "K1") (pin "2") (pinfunction "O_2") (pintype "passive"))
    )
    (net (code "69") (name "unconnected-(K1C-O-Pad7)") (class "Default")
      (node (ref "K1") (pin "7") (pinfunction "O_7") (pintype "passive"))
    )
    (net (code "70") (name "unconnected-(K2C-O-Pad7)") (class "Default")
      (node (ref "K2") (pin "7") (pinfunction "O_7") (pintype "passive"))
    )
    (net (code "71") (name "unconnected-(K3C-O-Pad7)") (class "Default")
      (node (ref "K3") (pin "7") (pinfunction "O_7") (pintype "passive"))
    )
    (net (code "72") (name "unconnected-(U$1-PadID)") (class "Default")
      (node (ref "U$1") (pin "ID") (pinfunction "ID_ID") (pintype "bidirectional"))
    )
    (net (code "73") (name "unconnected-(U$2-PadID)") (class "Default")
      (node (ref "U$2") (pin "ID") (pinfunction "ID_ID") (pintype "bidirectional"))
    )
    (net (code "74") (name "unconnected-(U$3-PadID)") (class "Default")
      (node (ref "U$3") (pin "ID") (pinfunction "ID_ID") (pintype "bidirectional"))
    )
  )
)
